# Arduino.net
KiCad netlist of a schematic drawn in Altium Designer
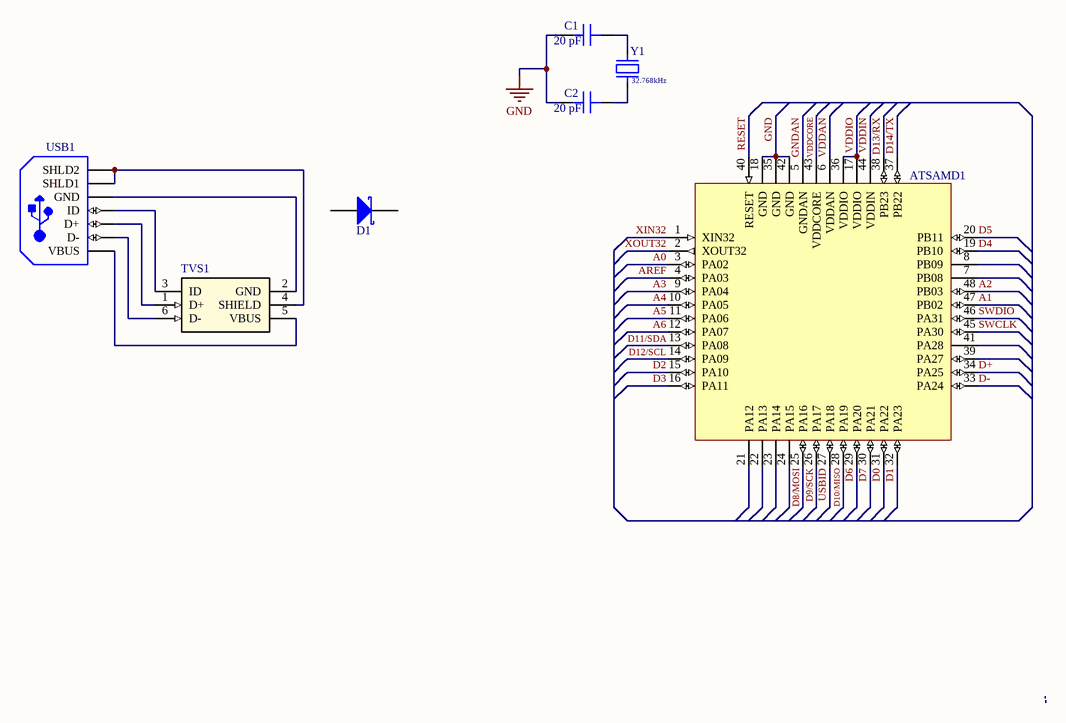
[diagram p0: Arduino.SchDoc]

(export (version "E")
  (design (tool "Eeschema 10.0.6"))
  (components
    (comp (ref "ATSAMD1")
      (value "ATSAMD21G18A-AU")
      (footprint "ATSAMD21G18-AU")
      (libsource (lib "Arduino Nano Every Symbols") (part "ATSAMD21G18A-AU"))
    )
    (comp (ref "C1")
      (value "20 pF")
      (footprint "Capacitor 20 pF SMT 0603")
      (description "20 pF ±5% 50V Ceramic Capacitor C0G, NP0 0603 (1608 Metric)")
      (fields (field (name "PART NUMBER") "CC0603JRNPO9BN200") (field (name "MANUFACTURER") "Yageo"))
      (libsource (lib "Arduino Nano Every Symbols") (part "Capacitor 20 pF SMT 0603"))
    )
    (comp (ref "C2")
      (value "20 pF")
      (footprint "Capacitor 20 pF SMT 0603")
      (description "20 pF ±5% 50V Ceramic Capacitor C0G, NP0 0603 (1608 Metric)")
      (fields (field (name "PART NUMBER") "CC0603JRNPO9BN200") (field (name "MANUFACTURER") "Yageo"))
      (libsource (lib "Arduino Nano Every Symbols") (part "Capacitor 20 pF SMT 0603"))
    )
    (comp (ref "D1")
      (value "NSR0530HT1G")
      (footprint "Schottky Diode 30V SMT")
      (description "Schottky Diode 30 V 500mA Surface Mount SOD-323")
      (fields (field (name "MANUFACTURER") "ON Semiconductor"))
      (libsource (lib "Arduino Nano Every Symbols") (part "Schottky Diode 30V"))
    )
    (comp (ref "TVS1")
      (value "RCLAMP0504FA.TCT")
      (footprint "RCLAMP0504FA.TCT")
      (description "25V Clamp 6A (8/20µs) Ipp Tvs Diode Surface Mount SC-70-6")
      (libsource (lib "Arduino Nano Every Symbols") (part "RCLAMP0504FA.TCT"))
    )
    (comp (ref "USB1")
      (value "USB3106-30-0230-A")
      (libsource (lib "Arduino Nano Every Symbols") (part "USB Micro-AB Connector B"))
    )
    (comp (ref "Y1")
      (value "32.768kHz")
      (footprint "ABS07-120-32.768KHZ-T A")
      (description "32.768 kHz ±20ppm Crystal 6pF 55 kOhms 2-SMD, No Lead")
      (fields
        (field (name "PART NUMBER") "ABS07-120-32.768KHZ-T")
        (field (name "MANUFACTURER") "Abracon LLC")
      )
      (libsource (lib "Arduino Nano Every Symbols") (part "Abracon Crystal ABS07"))
    )
  )
  (nets
    (net (code "1") (name "/A0") (class "Default")
      (node (ref "ATSAMD1") (pin "3") (pinfunction "PA02_3") (pintype "bidirectional"))
    )
    (net (code "2") (name "/A1") (class "Default")
      (node (ref "ATSAMD1") (pin "47") (pinfunction "PB02_47") (pintype "bidirectional"))
    )
    (net (code "3") (name "/A2") (class "Default")
      (node (ref "ATSAMD1") (pin "48") (pinfunction "PB03_48") (pintype "bidirectional"))
    )
    (net (code "4") (name "/A3") (class "Default")
      (node (ref "ATSAMD1") (pin "9") (pinfunction "PA04_9") (pintype "bidirectional"))
    )
    (net (code "5") (name "/A4") (class "Default")
      (node (ref "ATSAMD1") (pin "10") (pinfunction "PA05_10") (pintype "bidirectional"))
    )
    (net (code "6") (name "/A5") (class "Default")
      (node (ref "ATSAMD1") (pin "11") (pinfunction "PA06_11") (pintype "bidirectional"))
    )
    (net (code "7") (name "/A6") (class "Default")
      (node (ref "ATSAMD1") (pin "12") (pinfunction "PA07_12") (pintype "bidirectional"))
    )
    (net (code "8") (name "/AREF") (class "Default")
      (node (ref "ATSAMD1") (pin "4") (pinfunction "PA03_4") (pintype "bidirectional"))
    )
    (net (code "9") (name "/D+") (class "Default")
      (node (ref "ATSAMD1") (pin "34") (pinfunction "PA25_34") (pintype "bidirectional"))
    )
    (net (code "10") (name "/D-") (class "Default")
      (node (ref "ATSAMD1") (pin "33") (pinfunction "PA24_33") (pintype "bidirectional"))
    )
    (net (code "11") (name "/D0") (class "Default")
      (node (ref "ATSAMD1") (pin "31") (pinfunction "PA22_31") (pintype "bidirectional"))
    )
    (net (code "12") (name "/D1") (class "Default")
      (node (ref "ATSAMD1") (pin "32") (pinfunction "PA23_32") (pintype "bidirectional"))
    )
    (net (code "13") (name "/D2") (class "Default")
      (node (ref "ATSAMD1") (pin "15") (pinfunction "PA10_15") (pintype "bidirectional"))
    )
    (net (code "14") (name "/D3") (class "Default")
      (node (ref "ATSAMD1") (pin "16") (pinfunction "PA11_16") (pintype "bidirectional"))
    )
    (net (code "15") (name "/D4") (class "Default")
      (node (ref "ATSAMD1") (pin "19") (pinfunction "PB10_19") (pintype "bidirectional"))
    )
    (net (code "16") (name "/D5") (class "Default")
      (node (ref "ATSAMD1") (pin "20") (pinfunction "PB11_20") (pintype "bidirectional"))
    )
    (net (code "17") (name "/D6") (class "Default")
      (node (ref "ATSAMD1") (pin "29") (pinfunction "PA20_29") (pintype "bidirectional"))
    )
    (net (code "18") (name "/D7") (class "Default")
      (node (ref "ATSAMD1") (pin "30") (pinfunction "PA21_30") (pintype "bidirectional"))
    )
    (net (code "19") (name "/D8{slash}MOSI") (class "Default")
      (node (ref "ATSAMD1") (pin "25") (pinfunction "PA16_25") (pintype "bidirectional"))
    )
    (net (code "20") (name "/D9{slash}SCK") (class "Default")
      (node (ref "ATSAMD1") (pin "26") (pinfunction "PA17_26") (pintype "bidirectional"))
    )
    (net (code "21") (name "/D10{slash}MISO") (class "Default")
      (node (ref "ATSAMD1") (pin "28") (pinfunction "PA19_28") (pintype "bidirectional"))
    )
    (net (code "22") (name "/D11{slash}SDA") (class "Default")
      (node (ref "ATSAMD1") (pin "13") (pinfunction "PA08_13") (pintype "bidirectional"))
    )
    (net (code "23") (name "/D12{slash}SCL") (class "Default")
      (node (ref "ATSAMD1") (pin "14") (pinfunction "PA09_14") (pintype "bidirectional"))
    )
    (net (code "24") (name "/D13{slash}RX") (class "Default")
      (node (ref "ATSAMD1") (pin "38") (pinfunction "PB23_38") (pintype "bidirectional"))
    )
    (net (code "25") (name "/D14{slash}TX") (class "Default")
      (node (ref "ATSAMD1") (pin "37") (pinfunction "PB22_37") (pintype "bidirectional"))
    )
    (net (code "26") (name "/GNDAN") (class "Default")
      (node (ref "ATSAMD1") (pin "5") (pinfunction "GNDAN_5") (pintype "power_in"))
    )
    (net (code "27") (name "/RESET") (class "Default")
      (node (ref "ATSAMD1") (pin "40") (pinfunction "RESET_40") (pintype "input"))
    )
    (net (code "28") (name "/SWCLK") (class "Default")
      (node (ref "ATSAMD1") (pin "45") (pinfunction "PA30_45") (pintype "bidirectional"))
    )
    (net (code "29") (name "/SWDIO") (class "Default")
      (node (ref "ATSAMD1") (pin "46") (pinfunction "PA31_46") (pintype "bidirectional"))
    )
    (net (code "30") (name "/USBID") (class "Default")
      (node (ref "ATSAMD1") (pin "27") (pinfunction "PA18_27") (pintype "bidirectional"))
    )
    (net (code "31") (name "/VDDAN") (class "Default")
      (node (ref "ATSAMD1") (pin "6") (pinfunction "VDDAN_6") (pintype "power_in"))
    )
    (net (code "32") (name "/VDDCORE") (class "Default")
      (node (ref "ATSAMD1") (pin "43") (pinfunction "VDDCORE_43") (pintype "power_in"))
    )
    (net (code "33") (name "/VDDIN") (class "Default")
      (node (ref "ATSAMD1") (pin "44") (pinfunction "VDDIN_44") (pintype "power_in"))
    )
    (net (code "34") (name "/VDDIO") (class "Default")
      (node (ref "ATSAMD1") (pin "17") (pinfunction "VDDIO_17") (pintype "power_in"))
      (node (ref "ATSAMD1") (pin "36") (pinfunction "VDDIO_36") (pintype "power_in"))
    )
    (net (code "35") (name "/XIN32") (class "Default")
      (node (ref "ATSAMD1") (pin "1") (pinfunction "XIN32_1") (pintype "input"))
    )
    (net (code "36") (name "/XOUT32") (class "Default")
      (node (ref "ATSAMD1") (pin "2") (pinfunction "XOUT32_2") (pintype "output"))
    )
    (net (code "37") (name "GND") (class "Default")
      (node (ref "ATSAMD1") (pin "18") (pinfunction "GND_18") (pintype "power_in"))
      (node (ref "ATSAMD1") (pin "35") (pinfunction "GND_35") (pintype "power_in"))
      (node (ref "ATSAMD1") (pin "42") (pinfunction "GND_42") (pintype "power_in"))
      (node (ref "C1") (pin "1") (pinfunction "1_1") (pintype "passive"))
      (node (ref "C2") (pin "1") (pinfunction "1_1") (pintype "passive"))
    )
    (net (code "38") (name "Net-(C1-Pad2)") (class "Default")
      (node (ref "C1") (pin "2") (pinfunction "2_2") (pintype "passive"))
      (node (ref "Y1") (pin "2") (pinfunction "2_2") (pintype "passive"))
    )
    (net (code "39") (name "Net-(C2-Pad2)") (class "Default")
      (node (ref "C2") (pin "2") (pinfunction "2_2") (pintype "passive"))
      (node (ref "Y1") (pin "1") (pinfunction "1_1") (pintype "passive"))
    )
    (net (code "40") (name "Net-(TVS1-D+)") (class "Default")
      (node (ref "TVS1") (pin "1") (pinfunction "D+_1") (pintype "input"))
      (node (ref "USB1") (pin "3") (pinfunction "D+_3") (pintype "bidirectional"))
    )
    (net (code "41") (name "Net-(TVS1-D-)") (class "Default")
      (node (ref "TVS1") (pin "6") (pinfunction "D-_6") (pintype "input"))
      (node (ref "USB1") (pin "2") (pinfunction "D-_2") (pintype "bidirectional"))
    )
    (net (code "42") (name "Net-(TVS1-GND)") (class "Default")
      (node (ref "TVS1") (pin "2") (pinfunction "GND_2") (pintype "power_in"))
      (node (ref "USB1") (pin "5") (pinfunction "GND_5") (pintype "power_in"))
    )
    (net (code "43") (name "Net-(TVS1-ID)") (class "Default")
      (node (ref "TVS1") (pin "3") (pinfunction "ID_3") (pintype "passive"))
      (node (ref "USB1") (pin "4") (pinfunction "ID_4") (pintype "bidirectional"))
    )
    (net (code "44") (name "Net-(TVS1-SHIELD)") (class "Default")
      (node (ref "TVS1") (pin "4") (pinfunction "SHIELD_4") (pintype "power_in"))
      (node (ref "USB1") (pin "6") (pinfunction "SHLD1_6") (pintype "power_in"))
      (node (ref "USB1") (pin "7") (pinfunction "SHLD2_7") (pintype "power_in"))
    )
    (net (code "45") (name "Net-(TVS1-VBUS)") (class "Default")
      (node (ref "TVS1") (pin "5") (pinfunction "VBUS_5") (pintype "power_in"))
      (node (ref "USB1") (pin "1") (pinfunction "VBUS_1") (pintype "power_in"))
    )
    (net (code "46") (name "unconnected-(ATSAMD1-PA12-Pad21)") (class "Default")
      (node (ref "ATSAMD1") (pin "21") (pinfunction "PA12_21") (pintype "tri_state"))
    )
    (net (code "47") (name "unconnected-(ATSAMD1-PA13-Pad22)") (class "Default")
      (node (ref "ATSAMD1") (pin "22") (pinfunction "PA13_22") (pintype "tri_state"))
    )
    (net (code "48") (name "unconnected-(ATSAMD1-PA14-Pad23)") (class "Default")
      (node (ref "ATSAMD1") (pin "23") (pinfunction "PA14_23") (pintype "tri_state"))
    )
    (net (code "49") (name "unconnected-(ATSAMD1-PA15-Pad24)") (class "Default")
      (node (ref "ATSAMD1") (pin "24") (pinfunction "PA15_24") (pintype "tri_state"))
    )
    (net (code "50") (name "unconnected-(ATSAMD1-PA27-Pad39)") (class "Default")
      (node (ref "ATSAMD1") (pin "39") (pinfunction "PA27_39") (pintype "bidirectional"))
    )
    (net (code "51") (name "unconnected-(ATSAMD1-PA28-Pad41)") (class "Default")
      (node (ref "ATSAMD1") (pin "41") (pinfunction "PA28_41") (pintype "tri_state"))
    )
    (net (code "52") (name "unconnected-(ATSAMD1-PB08-Pad7)") (class "Default")
      (node (ref "ATSAMD1") (pin "7") (pinfunction "PB08_7") (pintype "tri_state"))
    )
    (net (code "53") (name "unconnected-(ATSAMD1-PB09-Pad8)") (class "Default")
      (node (ref "ATSAMD1") (pin "8") (pinfunction "PB09_8") (pintype "tri_state"))
    )
    (net (code "54") (name "unconnected-(D1-A-Pad3)") (class "Default")
      (node (ref "D1") (pin "3") (pinfunction "A_3") (pintype "passive"))
    )
    (net (code "55") (name "unconnected-(D1-K-Pad1)") (class "Default")
      (node (ref "D1") (pin "1") (pinfunction "K_1") (pintype "passive"))
    )
  )
)
